# zx81b.net
KiCad netlist of a schematic drawn in EAGLE
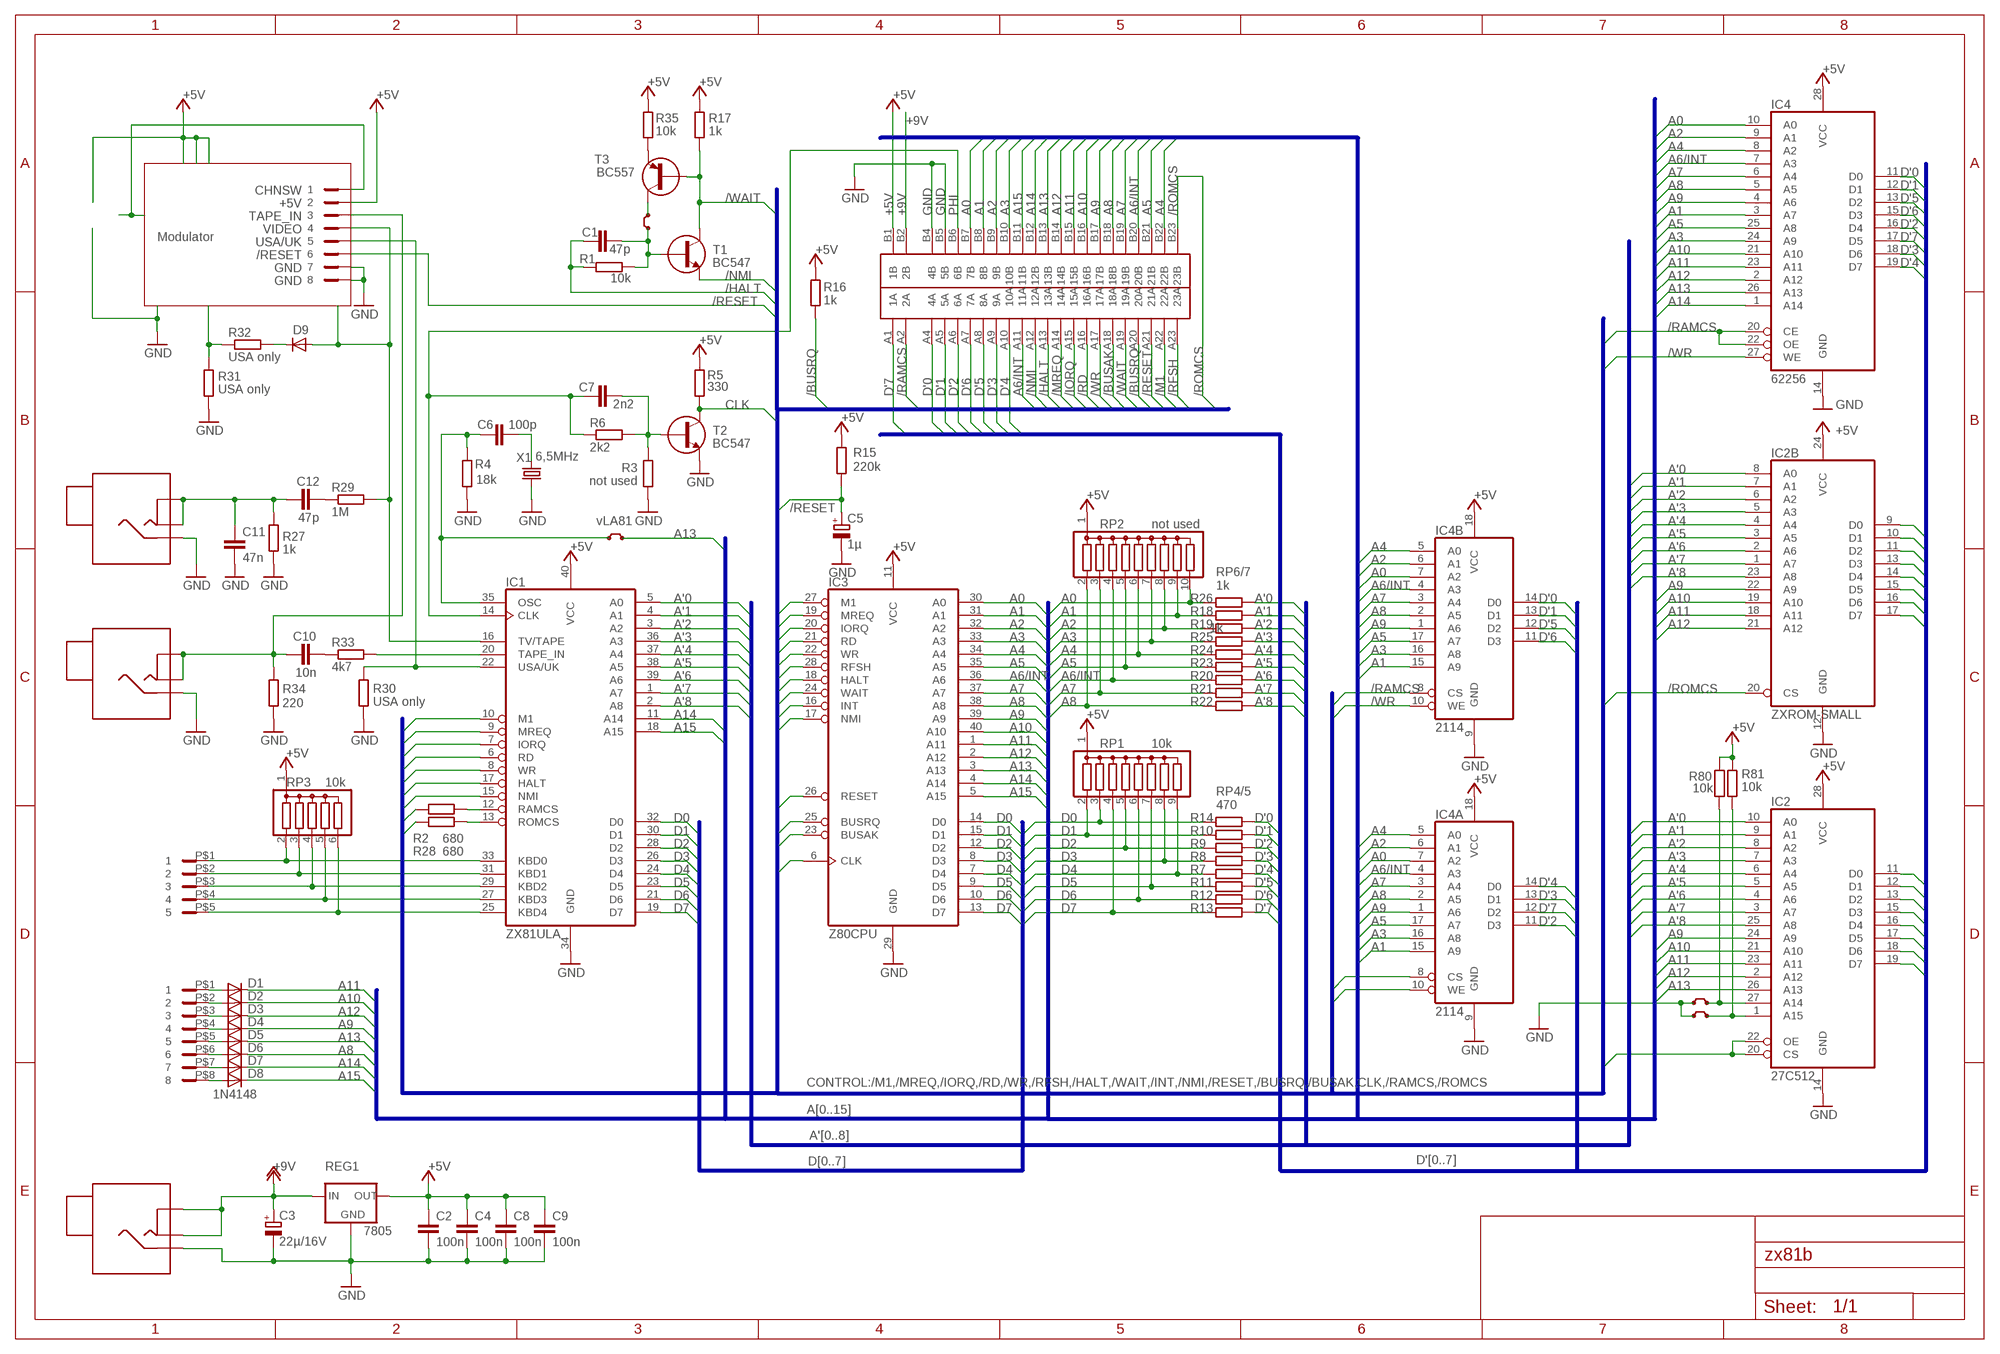
[diagram p0: schematic, sheet 1]

(export (version "E")
  (design (tool "Eeschema 10.0.6"))
  (components
    (comp (ref "C1")
      (value "47p")
      (footprint "eagle-import:C025-025X050")
      (libsource (lib "eagle-import") (part "C"))
    )
    (comp (ref "C2")
      (value "100n")
      (footprint "eagle-import:C025-025X050")
      (libsource (lib "eagle-import") (part "C"))
    )
    (comp (ref "C3")
      (value "22µ/16V")
      (footprint "eagle-import:E5-5")
      (libsource (lib "eagle-import") (part "CPOLE5-5"))
    )
    (comp (ref "C4")
      (value "100n")
      (footprint "eagle-import:C025-025X050")
      (libsource (lib "eagle-import") (part "C"))
    )
    (comp (ref "C5")
      (value "1µ")
      (footprint "eagle-import:E3,8-5")
      (libsource (lib "eagle-import") (part "CPOLE3,8-5"))
    )
    (comp (ref "C6")
      (value "100p")
      (footprint "eagle-import:C025-025X050")
      (libsource (lib "eagle-import") (part "C"))
    )
    (comp (ref "C7")
      (value "2n2")
      (footprint "eagle-import:C025-025X050")
      (libsource (lib "eagle-import") (part "C"))
    )
    (comp (ref "C8")
      (value "100n")
      (footprint "eagle-import:C025-025X050")
      (libsource (lib "eagle-import") (part "C"))
    )
    (comp (ref "C9")
      (value "100n")
      (footprint "eagle-import:C025-025X050")
      (libsource (lib "eagle-import") (part "C"))
    )
    (comp (ref "C10")
      (value "10n")
      (footprint "eagle-import:C025-025X050")
      (libsource (lib "eagle-import") (part "C"))
    )
    (comp (ref "C11")
      (value "47n")
      (footprint "eagle-import:C025-025X050")
      (libsource (lib "eagle-import") (part "C"))
    )
    (comp (ref "C12")
      (value "47p")
      (footprint "eagle-import:C025-025X050")
      (libsource (lib "eagle-import") (part "C"))
    )
    (comp (ref "D1")
      (value "1N4148")
      (footprint "eagle-import:D-TR-10")
      (libsource (lib "eagle-import") (part "DIODEDTR"))
    )
    (comp (ref "D2")
      (value "1N4148")
      (footprint "eagle-import:D-TR-10")
      (libsource (lib "eagle-import") (part "DIODEDTR"))
    )
    (comp (ref "D3")
      (value "1N4148")
      (footprint "eagle-import:D-TR-10")
      (libsource (lib "eagle-import") (part "DIODEDTR"))
    )
    (comp (ref "D4")
      (value "1N4148")
      (footprint "eagle-import:D-TR-10")
      (libsource (lib "eagle-import") (part "DIODEDTR"))
    )
    (comp (ref "D5")
      (value "1N4148")
      (footprint "eagle-import:D-TR-10")
      (libsource (lib "eagle-import") (part "DIODEDTR"))
    )
    (comp (ref "D6")
      (value "1N4148")
      (footprint "eagle-import:D-TR-10")
      (libsource (lib "eagle-import") (part "DIODEDTR"))
    )
    (comp (ref "D7")
      (value "1N4148")
      (footprint "eagle-import:D-TR-10")
      (libsource (lib "eagle-import") (part "DIODEDTR"))
    )
    (comp (ref "D8")
      (value "1N4148")
      (footprint "eagle-import:D-TR-10")
      (libsource (lib "eagle-import") (part "DIODEDTR"))
    )
    (comp (ref "D9")
      (value "DIODED15")
      (footprint "eagle-import:D15")
      (libsource (lib "eagle-import") (part "DIODED15"))
    )
    (comp (ref "IC1")
      (value "ZX81ULA")
      (footprint "eagle-import:DIL40")
      (libsource (lib "eagle-import") (part "ZX81ULA"))
    )
    (comp (ref "IC2")
      (value "27C512")
      (footprint "eagle-import:DIL28")
      (libsource (lib "eagle-import") (part "27C512"))
    )
    (comp (ref "IC2B")
      (value "ZXROM-SMALL")
      (footprint "eagle-import:DIL24")
      (libsource (lib "eagle-import") (part "ZXROM-SMALL"))
    )
    (comp (ref "IC3")
      (value "Z80CPU")
      (footprint "eagle-import:DIL40")
      (libsource (lib "eagle-import") (part "Z80CPU"))
    )
    (comp (ref "IC4")
      (value "62256")
      (footprint "eagle-import:DIL28")
      (libsource (lib "eagle-import") (part "62256"))
    )
    (comp (ref "IC4A")
      (value "2114")
      (footprint "eagle-import:DIL18")
      (libsource (lib "eagle-import") (part "2114"))
    )
    (comp (ref "IC4B")
      (value "2114")
      (footprint "eagle-import:DIL18")
      (libsource (lib "eagle-import") (part "2114"))
    )
    (comp (ref "JP1")
      (value "JUMPER")
      (footprint "eagle-import:JUMPER")
      (libsource (lib "eagle-import") (part "JUMPER"))
    )
    (comp (ref "JP2")
      (value "JUMPER")
      (footprint "eagle-import:JUMPER")
      (libsource (lib "eagle-import") (part "JUMPER"))
    )
    (comp (ref "JP3")
      (value "JUMPER")
      (footprint "eagle-import:JUMPER")
      (libsource (lib "eagle-import") (part "JUMPER"))
    )
    (comp (ref "JP4")
      (value "JUMPER")
      (footprint "eagle-import:JUMPER")
      (libsource (lib "eagle-import") (part "JUMPER"))
    )
    (comp (ref "K1")
      (value "ZX81CONN")
      (footprint "eagle-import:ZX81CON")
      (libsource (lib "eagle-import") (part "ZX81CONN"))
    )
    (comp (ref "K2")
      (value "MIC")
      (footprint "eagle-import:ZXKLINKE")
      (libsource (lib "eagle-import") (part "ZXKLINKE"))
    )
    (comp (ref "K3")
      (value "EAR")
      (footprint "eagle-import:ZXKLINKE")
      (libsource (lib "eagle-import") (part "ZXKLINKE"))
    )
    (comp (ref "K4")
      (value "DCIN")
      (footprint "eagle-import:ZXKLINKE")
      (libsource (lib "eagle-import") (part "ZXKLINKE"))
    )
    (comp (ref "K5")
      (value "PINHEAD-2X4")
      (footprint "eagle-import:PINHEAD2X4")
      (libsource (lib "eagle-import") (part "PINHEAD-2X4"))
    )
    (comp (ref "KB1")
      (value "ZXKBD5CON")
      (footprint "eagle-import:ZXKDB5")
      (libsource (lib "eagle-import") (part "ZXKBD5CON"))
    )
    (comp (ref "KB2")
      (value "ZXKBD8CON")
      (footprint "eagle-import:ZXKBD8")
      (libsource (lib "eagle-import") (part "ZXKBD8CON"))
    )
    (comp (ref "R1")
      (value "10k")
      (footprint "eagle-import:R207_12")
      (libsource (lib "eagle-import") (part "RR207/12"))
    )
    (comp (ref "R2")
      (value "680")
      (footprint "eagle-import:R207_12")
      (libsource (lib "eagle-import") (part "RR207/12"))
    )
    (comp (ref "R3")
      (value "not used")
      (footprint "eagle-import:R207_12")
      (libsource (lib "eagle-import") (part "RR207/12"))
    )
    (comp (ref "R4")
      (value "18k")
      (footprint "eagle-import:R207_12")
      (libsource (lib "eagle-import") (part "RR207/12"))
    )
    (comp (ref "R5")
      (value "330")
      (footprint "eagle-import:R207_12")
      (libsource (lib "eagle-import") (part "RR207/12"))
    )
    (comp (ref "R6")
      (value "2k2")
      (footprint "eagle-import:R207_12")
      (libsource (lib "eagle-import") (part "RR207/12"))
    )
    (comp (ref "R15")
      (value "220k")
      (footprint "eagle-import:R207_12")
      (libsource (lib "eagle-import") (part "RR207/12"))
    )
    (comp (ref "R16")
      (value "1k")
      (footprint "eagle-import:R207_12")
      (libsource (lib "eagle-import") (part "RR207/12"))
    )
    (comp (ref "R17")
      (value "1k")
      (footprint "eagle-import:R207_12")
      (libsource (lib "eagle-import") (part "RR207/12"))
    )
    (comp (ref "R27")
      (value "1k")
      (footprint "eagle-import:R207_12")
      (libsource (lib "eagle-import") (part "RR207/12"))
    )
    (comp (ref "R28")
      (value "680")
      (footprint "eagle-import:R207_12")
      (libsource (lib "eagle-import") (part "RR207/12"))
    )
    (comp (ref "R29")
      (value "1M")
      (footprint "eagle-import:R207_12")
      (libsource (lib "eagle-import") (part "RR207/12"))
    )
    (comp (ref "R30")
      (value "USA only")
      (footprint "eagle-import:R207_12")
      (libsource (lib "eagle-import") (part "RR207/12"))
    )
    (comp (ref "R31")
      (value "USA only")
      (footprint "eagle-import:R207_12")
      (libsource (lib "eagle-import") (part "RR207/12"))
    )
    (comp (ref "R32")
      (value "USA only")
      (footprint "eagle-import:R207_12")
      (libsource (lib "eagle-import") (part "RR207/12"))
    )
    (comp (ref "R33")
      (value "4k7")
      (footprint "eagle-import:R207_12")
      (libsource (lib "eagle-import") (part "RR207/12"))
    )
    (comp (ref "R34")
      (value "220")
      (footprint "eagle-import:R207_12")
      (libsource (lib "eagle-import") (part "RR207/12"))
    )
    (comp (ref "R35")
      (value "10k")
      (footprint "eagle-import:R207_12")
      (libsource (lib "eagle-import") (part "RR207/12"))
    )
    (comp (ref "R80")
      (value "10k")
      (footprint "eagle-import:R207_12")
      (libsource (lib "eagle-import") (part "RR207/12"))
    )
    (comp (ref "R81")
      (value "10k")
      (footprint "eagle-import:R207_12")
      (libsource (lib "eagle-import") (part "RR207/12"))
    )
    (comp (ref "REG1")
      (value "7805")
      (footprint "eagle-import:78XXL")
      (libsource (lib "eagle-import") (part "78XX"))
    )
    (comp (ref "RP1")
      (value "10k")
      (footprint "eagle-import:SIL9")
      (libsource (lib "eagle-import") (part "RSIL8"))
    )
    (comp (ref "RP2")
      (value "not used")
      (footprint "eagle-import:SIL10")
      (libsource (lib "eagle-import") (part "RSIL9"))
    )
    (comp (ref "RP3")
      (value "10k")
      (footprint "eagle-import:SIL6")
      (libsource (lib "eagle-import") (part "RSIL5"))
    )
    (comp (ref "RP4")
      (value "470")
      (footprint "eagle-import:SIL8P")
      (libsource (lib "eagle-import") (part "RSILP4"))
    )
    (comp (ref "RP5")
      (value "470")
      (footprint "eagle-import:SIL8P")
      (libsource (lib "eagle-import") (part "RSILP4"))
    )
    (comp (ref "RP6")
      (value "1k")
      (footprint "eagle-import:SIL8P")
      (libsource (lib "eagle-import") (part "RSILP4"))
    )
    (comp (ref "RP7")
      (value "1k")
      (footprint "eagle-import:SIL10P")
      (libsource (lib "eagle-import") (part "RSILP5"))
    )
    (comp (ref "T1")
      (value "BC547")
      (footprint "eagle-import:TO92")
      (libsource (lib "eagle-import") (part "T-NPN-BC547"))
    )
    (comp (ref "T2")
      (value "BC547")
      (footprint "eagle-import:TO92")
      (libsource (lib "eagle-import") (part "T-NPN-BC547"))
    )
    (comp (ref "T3")
      (value "BC557")
      (footprint "eagle-import:TO92")
      (libsource (lib "eagle-import") (part "T-PNP-BC557"))
    )
    (comp (ref "X1")
      (value "6,5MHz")
      (footprint "eagle-import:HC49")
      (libsource (lib "eagle-import") (part "CRYSTAL"))
    )
  )
  (nets
    (net (code "4") (name "+5V") (class "Default")
      (node (ref "C2") (pin "1") (pinfunction "1_1") (pintype "passive"))
      (node (ref "C4") (pin "1") (pinfunction "1_1") (pintype "passive"))
      (node (ref "C8") (pin "1") (pinfunction "1_1") (pintype "passive"))
      (node (ref "C9") (pin "1") (pinfunction "1_1") (pintype "passive"))
      (node (ref "IC1") (pin "40") (pinfunction "VCC_40") (pintype "power_in"))
      (node (ref "IC2") (pin "28") (pinfunction "VCC_28") (pintype "power_in"))
      (node (ref "IC2B") (pin "24") (pinfunction "VCC_24") (pintype "power_in"))
      (node (ref "IC3") (pin "11") (pinfunction "VCC_11") (pintype "power_in"))
      (node (ref "IC4") (pin "28") (pinfunction "VCC_28") (pintype "power_in"))
      (node (ref "IC4A") (pin "18") (pinfunction "VCC_18") (pintype "power_in"))
      (node (ref "IC4B") (pin "18") (pinfunction "VCC_18") (pintype "power_in"))
      (node (ref "K1") (pin "B1") (pinfunction "1B_B1") (pintype "bidirectional"))
      (node (ref "K5") (pin "2") (pinfunction "2_2") (pintype "bidirectional"))
      (node (ref "R15") (pin "2") (pinfunction "2_2") (pintype "passive"))
      (node (ref "R16") (pin "1") (pinfunction "1_1") (pintype "passive"))
      (node (ref "R17") (pin "2") (pinfunction "2_2") (pintype "passive"))
      (node (ref "R35") (pin "2") (pinfunction "2_2") (pintype "passive"))
      (node (ref "R5") (pin "2") (pinfunction "2_2") (pintype "passive"))
      (node (ref "R80") (pin "2") (pinfunction "2_2") (pintype "passive"))
      (node (ref "R81") (pin "2") (pinfunction "2_2") (pintype "passive"))
      (node (ref "REG1") (pin "OUT") (pinfunction "OUT_OUT") (pintype "passive"))
      (node (ref "RP1") (pin "1") (pinfunction "1_1") (pintype "passive"))
      (node (ref "RP2") (pin "1") (pinfunction "1_1") (pintype "passive"))
      (node (ref "RP3") (pin "1") (pinfunction "1_1") (pintype "passive"))
    )
    (net (code "5") (name "+9V") (class "Default")
      (node (ref "C3") (pin "+") (pinfunction "+_+") (pintype "passive"))
      (node (ref "K1") (pin "B2") (pinfunction "2B_B2") (pintype "bidirectional"))
      (node (ref "K4") (pin "1") (pinfunction "P$1_1") (pintype "bidirectional"))
      (node (ref "K4") (pin "1'") (pinfunction "P$1'_1'") (pintype "bidirectional"))
      (node (ref "REG1") (pin "IN") (pinfunction "IN_IN") (pintype "input"))
    )
    (net (code "6") (name "/A'0") (class "Default")
      (node (ref "IC1") (pin "5") (pinfunction "A0_5") (pintype "output"))
      (node (ref "IC2") (pin "10") (pinfunction "A0_10") (pintype "input"))
      (node (ref "IC2B") (pin "8") (pinfunction "A0_8") (pintype "input"))
      (node (ref "RP6") (pin "7") (pinfunction "1_7") (pintype "passive"))
    )
    (net (code "7") (name "/A'1") (class "Default")
      (node (ref "IC1") (pin "4") (pinfunction "A1_4") (pintype "output"))
      (node (ref "IC2") (pin "9") (pinfunction "A1_9") (pintype "input"))
      (node (ref "IC2B") (pin "7") (pinfunction "A1_7") (pintype "input"))
      (node (ref "RP7") (pin "2") (pinfunction "2_2") (pintype "passive"))
    )
    (net (code "8") (name "/A'2") (class "Default")
      (node (ref "IC1") (pin "3") (pinfunction "A2_3") (pintype "output"))
      (node (ref "IC2") (pin "8") (pinfunction "A2_8") (pintype "input"))
      (node (ref "IC2B") (pin "6") (pinfunction "A2_6") (pintype "input"))
      (node (ref "RP7") (pin "3") (pinfunction "1_3") (pintype "passive"))
    )
    (net (code "9") (name "/A'3") (class "Default")
      (node (ref "IC1") (pin "36") (pinfunction "A3_36") (pintype "output"))
      (node (ref "IC2") (pin "7") (pinfunction "A3_7") (pintype "input"))
      (node (ref "IC2B") (pin "5") (pinfunction "A3_5") (pintype "input"))
      (node (ref "RP6") (pin "5") (pinfunction "1_5") (pintype "passive"))
    )
    (net (code "10") (name "/A'4") (class "Default")
      (node (ref "IC1") (pin "37") (pinfunction "A4_37") (pintype "output"))
      (node (ref "IC2") (pin "6") (pinfunction "A4_6") (pintype "input"))
      (node (ref "IC2B") (pin "4") (pinfunction "A4_4") (pintype "input"))
      (node (ref "RP6") (pin "3") (pinfunction "1_3") (pintype "passive"))
    )
    (net (code "11") (name "/A'5") (class "Default")
      (node (ref "IC1") (pin "38") (pinfunction "A5_38") (pintype "output"))
      (node (ref "IC2") (pin "5") (pinfunction "A5_5") (pintype "input"))
      (node (ref "IC2B") (pin "3") (pinfunction "A5_3") (pintype "input"))
      (node (ref "RP6") (pin "1") (pinfunction "1_1") (pintype "passive"))
    )
    (net (code "12") (name "/A'6") (class "Default")
      (node (ref "IC1") (pin "39") (pinfunction "A6_39") (pintype "output"))
      (node (ref "IC2") (pin "4") (pinfunction "A6_4") (pintype "input"))
      (node (ref "IC2B") (pin "2") (pinfunction "A6_2") (pintype "input"))
      (node (ref "RP7") (pin "5") (pinfunction "1_5") (pintype "passive"))
    )
    (net (code "13") (name "/A'7") (class "Default")
      (node (ref "IC1") (pin "1") (pinfunction "A7_1") (pintype "output"))
      (node (ref "IC2") (pin "3") (pinfunction "A7_3") (pintype "input"))
      (node (ref "IC2B") (pin "1") (pinfunction "A7_1") (pintype "input"))
      (node (ref "RP7") (pin "7") (pinfunction "1_7") (pintype "passive"))
    )
    (net (code "14") (name "/A'8") (class "Default")
      (node (ref "IC1") (pin "2") (pinfunction "A8_2") (pintype "output"))
      (node (ref "IC2") (pin "25") (pinfunction "A8_25") (pintype "input"))
      (node (ref "IC2B") (pin "23") (pinfunction "A8_23") (pintype "input"))
      (node (ref "RP7") (pin "9") (pinfunction "1_9") (pintype "passive"))
    )
    (net (code "16") (name "/A0") (class "Default")
      (node (ref "IC3") (pin "30") (pinfunction "A0_30") (pintype "output"))
      (node (ref "IC4") (pin "10") (pinfunction "A0_10") (pintype "input"))
      (node (ref "IC4A") (pin "7") (pinfunction "A2_7") (pintype "output"))
      (node (ref "IC4B") (pin "7") (pinfunction "A2_7") (pintype "output"))
      (node (ref "K1") (pin "B7") (pinfunction "7B_B7") (pintype "bidirectional"))
      (node (ref "RP2") (pin "10") (pinfunction "10_10") (pintype "passive"))
      (node (ref "RP6") (pin "8") (pinfunction "2_8") (pintype "passive"))
    )
    (net (code "17") (name "/A1") (class "Default")
      (node (ref "IC3") (pin "31") (pinfunction "A1_31") (pintype "output"))
      (node (ref "IC4") (pin "3") (pinfunction "A7_3") (pintype "input"))
      (node (ref "IC4A") (pin "15") (pinfunction "A9_15") (pintype "output"))
      (node (ref "IC4B") (pin "15") (pinfunction "A9_15") (pintype "output"))
      (node (ref "K1") (pin "B8") (pinfunction "8B_B8") (pintype "bidirectional"))
      (node (ref "RP2") (pin "9") (pinfunction "9_9") (pintype "passive"))
      (node (ref "RP7") (pin "1") (pinfunction "1_1") (pintype "passive"))
    )
    (net (code "18") (name "/A2") (class "Default")
      (node (ref "IC3") (pin "32") (pinfunction "A2_32") (pintype "output"))
      (node (ref "IC4") (pin "9") (pinfunction "A1_9") (pintype "input"))
      (node (ref "IC4A") (pin "6") (pinfunction "A1_6") (pintype "output"))
      (node (ref "IC4B") (pin "6") (pinfunction "A1_6") (pintype "output"))
      (node (ref "K1") (pin "B9") (pinfunction "9B_B9") (pintype "bidirectional"))
      (node (ref "RP2") (pin "8") (pinfunction "8_8") (pintype "passive"))
      (node (ref "RP7") (pin "4") (pinfunction "2_4") (pintype "passive"))
    )
    (net (code "19") (name "/A3") (class "Default")
      (node (ref "IC3") (pin "33") (pinfunction "A3_33") (pintype "output"))
      (node (ref "IC4") (pin "24") (pinfunction "A9_24") (pintype "input"))
      (node (ref "IC4A") (pin "16") (pinfunction "A8_16") (pintype "output"))
      (node (ref "IC4B") (pin "16") (pinfunction "A8_16") (pintype "output"))
      (node (ref "K1") (pin "B10") (pinfunction "10B_B10") (pintype "bidirectional"))
      (node (ref "RP2") (pin "7") (pinfunction "7_7") (pintype "passive"))
      (node (ref "RP6") (pin "6") (pinfunction "2_6") (pintype "passive"))
    )
    (net (code "20") (name "/A4") (class "Default")
      (node (ref "IC3") (pin "34") (pinfunction "A4_34") (pintype "output"))
      (node (ref "IC4") (pin "8") (pinfunction "A2_8") (pintype "input"))
      (node (ref "IC4A") (pin "5") (pinfunction "A0_5") (pintype "output"))
      (node (ref "IC4B") (pin "5") (pinfunction "A0_5") (pintype "output"))
      (node (ref "K1") (pin "B22") (pinfunction "22B_B22") (pintype "bidirectional"))
      (node (ref "RP2") (pin "6") (pinfunction "6_6") (pintype "passive"))
      (node (ref "RP6") (pin "4") (pinfunction "2_4") (pintype "passive"))
    )
    (net (code "21") (name "/A5") (class "Default")
      (node (ref "IC3") (pin "35") (pinfunction "A5_35") (pintype "output"))
      (node (ref "IC4") (pin "25") (pinfunction "A8_25") (pintype "input"))
      (node (ref "IC4A") (pin "17") (pinfunction "A7_17") (pintype "output"))
      (node (ref "IC4B") (pin "17") (pinfunction "A7_17") (pintype "output"))
      (node (ref "K1") (pin "B21") (pinfunction "21B_B21") (pintype "bidirectional"))
      (node (ref "RP2") (pin "5") (pinfunction "5_5") (pintype "passive"))
      (node (ref "RP6") (pin "2") (pinfunction "2_2") (pintype "passive"))
    )
    (net (code "22") (name "/A6{slash}INT") (class "Default")
      (node (ref "IC3") (pin "16") (pinfunction "INT_16") (pintype "input"))
      (node (ref "IC3") (pin "36") (pinfunction "A6_36") (pintype "output"))
      (node (ref "IC4") (pin "7") (pinfunction "A3_7") (pintype "input"))
      (node (ref "IC4A") (pin "4") (pinfunction "A3_4") (pintype "output"))
      (node (ref "IC4B") (pin "4") (pinfunction "A3_4") (pintype "output"))
      (node (ref "K1") (pin "A11") (pinfunction "11A_A11") (pintype "bidirectional"))
      (node (ref "K1") (pin "B20") (pinfunction "20B_B20") (pintype "bidirectional"))
      (node (ref "RP2") (pin "4") (pinfunction "4_4") (pintype "passive"))
      (node (ref "RP7") (pin "6") (pinfunction "2_6") (pintype "passive"))
    )
    (net (code "23") (name "/A7") (class "Default")
      (node (ref "IC3") (pin "37") (pinfunction "A7_37") (pintype "output"))
      (node (ref "IC4") (pin "6") (pinfunction "A4_6") (pintype "input"))
      (node (ref "IC4A") (pin "3") (pinfunction "A4_3") (pintype "output"))
      (node (ref "IC4B") (pin "3") (pinfunction "A4_3") (pintype "output"))
      (node (ref "K1") (pin "B19") (pinfunction "19B_B19") (pintype "bidirectional"))
      (node (ref "RP2") (pin "3") (pinfunction "3_3") (pintype "passive"))
      (node (ref "RP7") (pin "8") (pinfunction "2_8") (pintype "passive"))
    )
    (net (code "24") (name "/A8") (class "Default")
      (node (ref "D6") (pin "C") (pinfunction "C_C") (pintype "passive"))
      (node (ref "IC3") (pin "38") (pinfunction "A8_38") (pintype "output"))
      (node (ref "IC4") (pin "5") (pinfunction "A5_5") (pintype "input"))
      (node (ref "IC4A") (pin "2") (pinfunction "A5_2") (pintype "output"))
      (node (ref "IC4B") (pin "2") (pinfunction "A5_2") (pintype "output"))
      (node (ref "K1") (pin "B18") (pinfunction "18B_B18") (pintype "bidirectional"))
      (node (ref "RP2") (pin "2") (pinfunction "2_2") (pintype "passive"))
      (node (ref "RP7") (pin "10") (pinfunction "2_10") (pintype "passive"))
    )
    (net (code "25") (name "/A9") (class "Default")
      (node (ref "D4") (pin "C") (pinfunction "C_C") (pintype "passive"))
      (node (ref "IC2") (pin "24") (pinfunction "A9_24") (pintype "input"))
      (node (ref "IC2B") (pin "22") (pinfunction "A9_22") (pintype "input"))
      (node (ref "IC3") (pin "39") (pinfunction "A9_39") (pintype "output"))
      (node (ref "IC4") (pin "4") (pinfunction "A6_4") (pintype "input"))
      (node (ref "IC4A") (pin "1") (pinfunction "A6_1") (pintype "output"))
      (node (ref "IC4B") (pin "1") (pinfunction "A6_1") (pintype "output"))
      (node (ref "K1") (pin "B17") (pinfunction "17B_B17") (pintype "bidirectional"))
    )
    (net (code "26") (name "/A10") (class "Default")
      (node (ref "D2") (pin "C") (pinfunction "C_C") (pintype "passive"))
      (node (ref "IC2") (pin "21") (pinfunction "A10_21") (pintype "input"))
      (node (ref "IC2B") (pin "19") (pinfunction "A10_19") (pintype "input"))
      (node (ref "IC3") (pin "40") (pinfunction "A10_40") (pintype "output"))
      (node (ref "IC4") (pin "21") (pinfunction "A10_21") (pintype "input"))
      (node (ref "K1") (pin "B16") (pinfunction "16B_B16") (pintype "bidirectional"))
    )
    (net (code "27") (name "/A11") (class "Default")
      (node (ref "D1") (pin "C") (pinfunction "C_C") (pintype "passive"))
      (node (ref "IC2") (pin "23") (pinfunction "A11_23") (pintype "input"))
      (node (ref "IC2B") (pin "18") (pinfunction "A11_18") (pintype "input"))
      (node (ref "IC3") (pin "1") (pinfunction "A11_1") (pintype "output"))
      (node (ref "IC4") (pin "23") (pinfunction "A11_23") (pintype "input"))
      (node (ref "K1") (pin "B15") (pinfunction "15B_B15") (pintype "bidirectional"))
    )
    (net (code "28") (name "/A12") (class "Default")
      (node (ref "D3") (pin "C") (pinfunction "C_C") (pintype "passive"))
      (node (ref "IC2") (pin "2") (pinfunction "A12_2") (pintype "input"))
      (node (ref "IC2B") (pin "21") (pinfunction "A12_21") (pintype "input"))
      (node (ref "IC3") (pin "2") (pinfunction "A12_2") (pintype "output"))
      (node (ref "IC4") (pin "2") (pinfunction "A12_2") (pintype "input"))
      (node (ref "K1") (pin "B14") (pinfunction "14B_B14") (pintype "bidirectional"))
    )
    (net (code "29") (name "/A13") (class "Default")
      (node (ref "D5") (pin "C") (pinfunction "C_C") (pintype "passive"))
      (node (ref "IC2") (pin "26") (pinfunction "A13_26") (pintype "input"))
      (node (ref "IC3") (pin "3") (pinfunction "A13_3") (pintype "output"))
      (node (ref "IC4") (pin "26") (pinfunction "A13_26") (pintype "input"))
      (node (ref "JP3") (pin "2") (pinfunction "P$2_2") (pintype "bidirectional"))
      (node (ref "K1") (pin "B13") (pinfunction "13B_B13") (pintype "bidirectional"))
    )
    (net (code "30") (name "/A14") (class "Default")
      (node (ref "D7") (pin "C") (pinfunction "C_C") (pintype "passive"))
      (node (ref "IC1") (pin "11") (pinfunction "A14_11") (pintype "output"))
      (node (ref "IC3") (pin "4") (pinfunction "A14_4") (pintype "output"))
      (node (ref "IC4") (pin "1") (pinfunction "A14_1") (pintype "input"))
      (node (ref "K1") (pin "B12") (pinfunction "12B_B12") (pintype "bidirectional"))
    )
    (net (code "31") (name "/A15") (class "Default")
      (node (ref "D8") (pin "C") (pinfunction "C_C") (pintype "passive"))
      (node (ref "IC1") (pin "18") (pinfunction "A15_18") (pintype "output"))
      (node (ref "IC3") (pin "5") (pinfunction "A15_5") (pintype "output"))
      (node (ref "K1") (pin "B11") (pinfunction "11B_B11") (pintype "bidirectional"))
    )
    (net (code "33") (name "/CHNSW") (class "Default")
      (node (ref "K5") (pin "1") (pinfunction "1_1") (pintype "bidirectional"))
    )
    (net (code "34") (name "/CLK") (class "Default")
      (node (ref "IC3") (pin "6") (pinfunction "CLK_6") (pintype "input"))
      (node (ref "R5") (pin "1") (pinfunction "1_1") (pintype "passive"))
      (node (ref "T2") (pin "C") (pinfunction "C_C") (pintype "passive"))
    )
    (net (code "35") (name "/D'0") (class "Default")
      (node (ref "IC2") (pin "11") (pinfunction "D0_11") (pintype "bidirectional"))
      (node (ref "IC2B") (pin "9") (pinfunction "D0_9") (pintype "output"))
      (node (ref "IC4") (pin "11") (pinfunction "D0_11") (pintype "bidirectional"))
      (node (ref "IC4B") (pin "14") (pinfunction "D0_14") (pintype "bidirectional"))
      (node (ref "K1") (pin "A4") (pinfunction "4A_A4") (pintype "bidirectional"))
      (node (ref "RP5") (pin "8") (pinfunction "2_8") (pintype "passive"))
    )
    (net (code "36") (name "/D'1") (class "Default")
      (node (ref "IC2") (pin "12") (pinfunction "D1_12") (pintype "bidirectional"))
      (node (ref "IC2B") (pin "10") (pinfunction "D1_10") (pintype "output"))
      (node (ref "IC4") (pin "12") (pinfunction "D1_12") (pintype "bidirectional"))
      (node (ref "IC4B") (pin "13") (pinfunction "D1_13") (pintype "bidirectional"))
      (node (ref "K1") (pin "A5") (pinfunction "5A_A5") (pintype "bidirectional"))
      (node (ref "RP4") (pin "8") (pinfunction "2_8") (pintype "passive"))
    )
    (net (code "37") (name "/D'2") (class "Default")
      (node (ref "IC2") (pin "13") (pinfunction "D2_13") (pintype "bidirectional"))
      (node (ref "IC2B") (pin "11") (pinfunction "D2_11") (pintype "output"))
      (node (ref "IC4") (pin "16") (pinfunction "D4_16") (pintype "bidirectional"))
      (node (ref "IC4A") (pin "11") (pinfunction "D3_11") (pintype "bidirectional"))
      (node (ref "K1") (pin "A6") (pinfunction "6A_A6") (pintype "bidirectional"))
      (node (ref "RP4") (pin "6") (pinfunction "2_6") (pintype "passive"))
    )
    (net (code "38") (name "/D'3") (class "Default")
      (node (ref "IC2") (pin "15") (pinfunction "D3_15") (pintype "bidirectional"))
      (node (ref "IC2B") (pin "13") (pinfunction "D3_13") (pintype "output"))
      (node (ref "IC4") (pin "18") (pinfunction "D6_18") (pintype "bidirectional"))
      (node (ref "IC4A") (pin "13") (pinfunction "D1_13") (pintype "bidirectional"))
      (node (ref "K1") (pin "A9") (pinfunction "9A_A9") (pintype "bidirectional"))
      (node (ref "RP4") (pin "4") (pinfunction "2_4") (pintype "passive"))
    )
    (net (code "39") (name "/D'4") (class "Default")
      (node (ref "IC2") (pin "16") (pinfunction "D4_16") (pintype "bidirectional"))
      (node (ref "IC2B") (pin "14") (pinfunction "D4_14") (pintype "output"))
      (node (ref "IC4") (pin "19") (pinfunction "D7_19") (pintype "bidirectional"))
      (node (ref "IC4A") (pin "14") (pinfunction "D0_14") (pintype "bidirectional"))
      (node (ref "K1") (pin "A10") (pinfunction "10A_A10") (pintype "bidirectional"))
      (node (ref "RP4") (pin "1") (pinfunction "1_1") (pintype "passive"))
    )
    (net (code "40") (name "/D'5") (class "Default")
      (node (ref "IC2") (pin "17") (pinfunction "D5_17") (pintype "bidirectional"))
      (node (ref "IC2B") (pin "15") (pinfunction "D5_15") (pintype "output"))
      (node (ref "IC4") (pin "13") (pinfunction "D2_13") (pintype "bidirectional"))
      (node (ref "IC4B") (pin "12") (pinfunction "D2_12") (pintype "bidirectional"))
      (node (ref "K1") (pin "A8") (pinfunction "8A_A8") (pintype "bidirectional"))
      (node (ref "RP5") (pin "1") (pinfunction "1_1") (pintype "passive"))
    )
    (net (code "41") (name "/D'6") (class "Default")
      (node (ref "IC2") (pin "18") (pinfunction "D6_18") (pintype "bidirectional"))
      (node (ref "IC2B") (pin "16") (pinfunction "D6_16") (pintype "output"))
      (node (ref "IC4") (pin "15") (pinfunction "D3_15") (pintype "bidirectional"))
      (node (ref "IC4B") (pin "11") (pinfunction "D3_11") (pintype "bidirectional"))
      (node (ref "K1") (pin "A7") (pinfunction "7A_A7") (pintype "bidirectional"))
      (node (ref "RP5") (pin "4") (pinfunction "2_4") (pintype "passive"))
    )
    (net (code "42") (name "/D'7") (class "Default")
      (node (ref "IC2") (pin "19") (pinfunction "D7_19") (pintype "bidirectional"))
      (node (ref "IC2B") (pin "17") (pinfunction "D7_17") (pintype "output"))
      (node (ref "IC4") (pin "17") (pinfunction "D5_17") (pintype "bidirectional"))
      (node (ref "IC4A") (pin "12") (pinfunction "D2_12") (pintype "bidirectional"))
      (node (ref "K1") (pin "A1") (pinfunction "1A_A1") (pintype "bidirectional"))
      (node (ref "RP5") (pin "5") (pinfunction "1_5") (pintype "passive"))
    )
    (net (code "44") (name "/D0") (class "Default")
      (node (ref "IC1") (pin "32") (pinfunction "D0_32") (pintype "bidirectional"))
      (node (ref "IC3") (pin "14") (pinfunction "D0_14") (pintype "bidirectional"))
      (node (ref "RP1") (pin "3") (pinfunction "3_3") (pintype "passive"))
      (node (ref "RP5") (pin "7") (pinfunction "1_7") (pintype "passive"))
    )
    (net (code "45") (name "/D1") (class "Default")
      (node (ref "IC1") (pin "30") (pinfunction "D1_30") (pintype "bidirectional"))
      (node (ref "IC3") (pin "15") (pinfunction "D1_15") (pintype "bidirectional"))
      (node (ref "RP1") (pin "2") (pinfunction "2_2") (pintype "passive"))
      (node (ref "RP4") (pin "7") (pinfunction "1_7") (pintype "passive"))
    )
    (net (code "46") (name "/D2") (class "Default")
      (node (ref "IC1") (pin "28") (pinfunction "D2_28") (pintype "bidirectional"))
      (node (ref "IC3") (pin "12") (pinfunction "D2_12") (pintype "bidirectional"))
      (node (ref "RP1") (pin "5") (pinfunction "5_5") (pintype "passive"))
      (node (ref "RP4") (pin "5") (pinfunction "1_5") (pintype "passive"))
    )
    (net (code "47") (name "/D3") (class "Default")
      (node (ref "IC1") (pin "26") (pinfunction "D3_26") (pintype "bidirectional"))
      (node (ref "IC3") (pin "8") (pinfunction "D3_8") (pintype "bidirectional"))
      (node (ref "RP1") (pin "8") (pinfunction "8_8") (pintype "passive"))
      (node (ref "RP4") (pin "3") (pinfunction "1_3") (pintype "passive"))
    )
    (net (code "48") (name "/D4") (class "Default")
      (node (ref "IC1") (pin "24") (pinfunction "D4_24") (pintype "bidirectional"))
      (node (ref "IC3") (pin "7") (pinfunction "D4_7") (pintype "bidirectional"))
      (node (ref "RP1") (pin "9") (pinfunction "9_9") (pintype "passive"))
      (node (ref "RP4") (pin "2") (pinfunction "2_2") (pintype "passive"))
    )
    (net (code "49") (name "/D5") (class "Default")
      (node (ref "IC1") (pin "23") (pinfunction "D5_23") (pintype "bidirectional"))
      (node (ref "IC3") (pin "9") (pinfunction "D5_9") (pintype "bidirectional"))
      (node (ref "RP1") (pin "7") (pinfunction "7_7") (pintype "passive"))
      (node (ref "RP5") (pin "2") (pinfunction "2_2") (pintype "passive"))
    )
    (net (code "50") (name "/D6") (class "Default")
      (node (ref "IC1") (pin "21") (pinfunction "D6_21") (pintype "bidirectional"))
      (node (ref "IC3") (pin "10") (pinfunction "D6_10") (pintype "bidirectional"))
      (node (ref "RP1") (pin "6") (pinfunction "6_6") (pintype "passive"))
      (node (ref "RP5") (pin "3") (pinfunction "1_3") (pintype "passive"))
    )
    (net (code "51") (name "/D7") (class "Default")
      (node (ref "IC1") (pin "19") (pinfunction "D7_19") (pintype "bidirectional"))
      (node (ref "IC3") (pin "13") (pinfunction "D7_13") (pintype "bidirectional"))
      (node (ref "RP1") (pin "4") (pinfunction "4_4") (pintype "passive"))
      (node (ref "RP5") (pin "6") (pinfunction "2_6") (pintype "passive"))
    )
    (net (code "53") (name "/PHI") (class "Default")
      (node (ref "C7") (pin "1") (pinfunction "1_1") (pintype "passive"))
      (node (ref "IC1") (pin "14") (pinfunction "CLK_14") (pintype "input"))
      (node (ref "K1") (pin "B6") (pinfunction "6B_B6") (pintype "bidirectional"))
      (node (ref "R6") (pin "1") (pinfunction "1_1") (pintype "passive"))
    )
    (net (code "54") (name "/TAPE_IN") (class "Default")
      (node (ref "C10") (pin "1") (pinfunction "1_1") (pintype "passive"))
      (node (ref "K3") (pin "1") (pinfunction "P$1_1") (pintype "bidirectional"))
      (node (ref "K3") (pin "1'") (pinfunction "P$1'_1'") (pintype "bidirectional"))
      (node (ref "K5") (pin "3") (pinfunction "3_3") (pintype "bidirectional"))
      (node (ref "R34") (pin "2") (pinfunction "2_2") (pintype "passive"))
    )
    (net (code "55") (name "/USA{slash}UK") (class "Default")
      (node (ref "IC1") (pin "22") (pinfunction "USA/UK_22") (pintype "output"))
      (node (ref "K5") (pin "5") (pinfunction "5_5") (pintype "bidirectional"))
      (node (ref "R30") (pin "1") (pinfunction "1_1") (pintype "passive"))
    )
    (net (code "56") (name "/VIDEO") (class "Default")
      (node (ref "D9") (pin "A") (pinfunction "A_A") (pintype "passive"))
      (node (ref "IC1") (pin "16") (pinfunction "TV/TAPE_16") (pintype "output"))
      (node (ref "K5") (pin "4") (pinfunction "4_4") (pintype "bidirectional"))
      (node (ref "R29") (pin "2") (pinfunction "2_2") (pintype "passive"))
    )
    (net (code "58") (name "/{slash}BUSAK") (class "Default")
      (node (ref "IC3") (pin "23") (pinfunction "BUSAK_23") (pintype "output"))
      (node (ref "K1") (pin "A18") (pinfunction "18A_A18") (pintype "bidirectional"))
    )
    (net (code "59") (name "/{slash}BUSRQ") (class "Default")
      (node (ref "IC3") (pin "25") (pinfunction "BUSRQ_25") (pintype "input"))
      (node (ref "K1") (pin "A20") (pinfunction "20A_A20") (pintype "bidirectional"))
      (node (ref "R16") (pin "2") (pinfunction "2_2") (pintype "passive"))
    )
    (net (code "60") (name "/{slash}HALT") (class "Default")
      (node (ref "C1") (pin "1") (pinfunction "1_1") (pintype "passive"))
      (node (ref "IC1") (pin "17") (pinfunction "HALT_17") (pintype "output"))
      (node (ref "IC3") (pin "18") (pinfunction "HALT_18") (pintype "output"))
      (node (ref "K1") (pin "A13") (pinfunction "13A_A13") (pintype "bidirectional"))
      (node (ref "R1") (pin "1") (pinfunction "1_1") (pintype "passive"))
    )
    (net (code "61") (name "/{slash}IORQ") (class "Default")
      (node (ref "IC1") (pin "7") (pinfunction "IORQ_7") (pintype "output"))
      (node (ref "IC3") (pin "20") (pinfunction "IORQ_20") (pintype "output"))
      (node (ref "K1") (pin "A15") (pinfunction "15A_A15") (pintype "bidirectional"))
    )
    (net (code "62") (name "/{slash}M1") (class "Default")
      (node (ref "IC1") (pin "10") (pinfunction "M1_10") (pintype "output"))
      (node (ref "IC3") (pin "27") (pinfunction "M1_27") (pintype "output"))
      (node (ref "K1") (pin "A22") (pinfunction "22A_A22") (pintype "bidirectional"))
    )
    (net (code "63") (name "/{slash}MREQ") (class "Default")
      (node (ref "IC1") (pin "9") (pinfunction "MREQ_9") (pintype "output"))
      (node (ref "IC3") (pin "19") (pinfunction "MREQ_19") (pintype "output"))
      (node (ref "K1") (pin "A14") (pinfunction "14A_A14") (pintype "bidirectional"))
    )
    (net (code "64") (name "/{slash}NMI") (class "Default")
      (node (ref "IC1") (pin "15") (pinfunction "NMI_15") (pintype "input"))
      (node (ref "IC3") (pin "17") (pinfunction "NMI_17") (pintype "input"))
      (node (ref "K1") (pin "A12") (pinfunction "12A_A12") (pintype "bidirectional"))
      (node (ref "T1") (pin "E") (pinfunction "E_E") (pintype "passive"))
    )
    (net (code "65") (name "/{slash}RAMCS") (class "Default")
      (node (ref "IC4") (pin "20") (pinfunction "CE_20") (pintype "input"))
      (node (ref "IC4") (pin "22") (pinfunction "OE_22") (pintype "input"))
      (node (ref "IC4A") (pin "8") (pinfunction "CS_8") (pintype "output"))
      (node (ref "IC4B") (pin "8") (pinfunction "CS_8") (pintype "output"))
      (node (ref "K1") (pin "A2") (pinfunction "2A_A2") (pintype "bidirectional"))
      (node (ref "R2") (pin "2") (pinfunction "2_2") (pintype "passive"))
    )
    (net (code "66") (name "/{slash}RD") (class "Default")
      (node (ref "IC1") (pin "6") (pinfunction "RD_6") (pintype "output"))
      (node (ref "IC3") (pin "21") (pinfunction "RD_21") (pintype "output"))
      (node (ref "K1") (pin "A16") (pinfunction "16A_A16") (pintype "bidirectional"))
    )
    (net (code "67") (name "/{slash}RESET") (class "Default")
      (node (ref "C5") (pin "+") (pinfunction "+_+") (pintype "passive"))
      (node (ref "IC3") (pin "26") (pinfunction "RESET_26") (pintype "input"))
      (node (ref "K1") (pin "A21") (pinfunction "21A_A21") (pintype "bidirectional"))
      (node (ref "K5") (pin "6") (pinfunction "6_6") (pintype "bidirectional"))
      (node (ref "R15") (pin "1") (pinfunction "1_1") (pintype "passive"))
    )
    (net (code "68") (name "/{slash}RFSH") (class "Default")
      (node (ref "IC3") (pin "28") (pinfunction "RFSH_28") (pintype "output"))
      (node (ref "K1") (pin "A23") (pinfunction "23A_A23") (pintype "bidirectional"))
    )
    (net (code "69") (name "/{slash}ROMCS") (class "Default")
      (node (ref "IC2") (pin "20") (pinfunction "CS_20") (pintype "input"))
      (node (ref "IC2") (pin "22") (pinfunction "OE_22") (pintype "input"))
      (node (ref "IC2B") (pin "20") (pinfunction "CS_20") (pintype "output"))
      (node (ref "K1") (pin "B23") (pinfunction "23B_B23") (pintype "bidirectional"))
      (node (ref "R28") (pin "2") (pinfunction "2_2") (pintype "passive"))
    )
    (net (code "70") (name "/{slash}WAIT") (class "Default")
      (node (ref "IC3") (pin "24") (pinfunction "WAIT_24") (pintype "input"))
      (node (ref "K1") (pin "A19") (pinfunction "19A_A19") (pintype "bidirectional"))
      (node (ref "R17") (pin "1") (pinfunction "1_1") (pintype "passive"))
      (node (ref "T1") (pin "C") (pinfunction "C_C") (pintype "passive"))
      (node (ref "T3") (pin "B") (pinfunction "B_B") (pintype "passive"))
    )
    (net (code "71") (name "/{slash}WR") (class "Default")
      (node (ref "IC1") (pin "8") (pinfunction "WR_8") (pintype "output"))
      (node (ref "IC3") (pin "22") (pinfunction "WR_22") (pintype "output"))
      (node (ref "IC4") (pin "27") (pinfunction "WE_27") (pintype "input"))
      (node (ref "IC4A") (pin "10") (pinfunction "WE_10") (pintype "output"))
      (node (ref "IC4B") (pin "10") (pinfunction "WE_10") (pintype "output"))
      (node (ref "K1") (pin "A17") (pinfunction "17A_A17") (pintype "bidirectional"))
    )
    (net (code "72") (name "GND") (class "Default")
      (node (ref "C11") (pin "2") (pinfunction "2_2") (pintype "passive"))
      (node (ref "C2") (pin "2") (pinfunction "2_2") (pintype "passive"))
      (node (ref "C3") (pin "-") (pinfunction "-_-") (pintype "passive"))
      (node (ref "C4") (pin "2") (pinfunction "2_2") (pintype "passive"))
      (node (ref "C5") (pin "-") (pinfunction "-_-") (pintype "passive"))
      (node (ref "C8") (pin "2") (pinfunction "2_2") (pintype "passive"))
      (node (ref "C9") (pin "2") (pinfunction "2_2") (pintype "passive"))
      (node (ref "IC1") (pin "34") (pinfunction "GND_34") (pintype "power_in"))
      (node (ref "IC2") (pin "14") (pinfunction "GND_14") (pintype "power_in"))
      (node (ref "IC2B") (pin "12") (pinfunction "GND_12") (pintype "power_in"))
      (node (ref "IC3") (pin "29") (pinfunction "GND_29") (pintype "power_in"))
      (node (ref "IC4") (pin "14") (pinfunction "GND_14") (pintype "power_in"))
      (node (ref "IC4A") (pin "9") (pinfunction "GND_9") (pintype "power_in"))
      (node (ref "IC4B") (pin "9") (pinfunction "GND_9") (pintype "power_in"))
      (node (ref "JP1") (pin "1") (pinfunction "P$1_1") (pintype "bidirectional"))
      (node (ref "JP2") (pin "1") (pinfunction "P$1_1") (pintype "bidirectional"))
      (node (ref "K1") (pin "B4") (pinfunction "4B_B4") (pintype "bidirectional"))
      (node (ref "K1") (pin "B5") (pinfunction "5B_B5") (pintype "bidirectional"))
      (node (ref "K2") (pin "2") (pinfunction "P$2_2") (pintype "bidirectional"))
      (node (ref "K3") (pin "2") (pinfunction "P$2_2") (pintype "bidirectional"))
      (node (ref "K4") (pin "2") (pinfunction "P$2_2") (pintype "bidirectional"))
      (node (ref "K5") (pin "7") (pinfunction "7_7") (pintype "bidirectional"))
      (node (ref "K5") (pin "8") (pinfunction "8_8") (pintype "bidirectional"))
      (node (ref "R27") (pin "1") (pinfunction "1_1") (pintype "passive"))
      (node (ref "R3") (pin "1") (pinfunction "1_1") (pintype "passive"))
      (node (ref "R30") (pin "2") (pinfunction "2_2") (pintype "passive"))
      (node (ref "R31") (pin "1") (pinfunction "1_1") (pintype "passive"))
      (node (ref "R34") (pin "1") (pinfunction "1_1") (pintype "passive"))
      (node (ref "R4") (pin "1") (pinfunction "1_1") (pintype "passive"))
      (node (ref "REG1") (pin "GND") (pinfunction "GND_GND") (pintype "input"))
      (node (ref "T2") (pin "E") (pinfunction "E_E") (pintype "passive"))
      (node (ref "X1") (pin "1") (pinfunction "1_1") (pintype "passive"))
    )
    (net (code "73") (name "Net-(C6-Pad2)") (class "Default")
      (node (ref "C6") (pin "2") (pinfunction "2_2") (pintype "passive"))
      (node (ref "X1") (pin "2") (pinfunction "2_2") (pintype "passive"))
    )
    (net (code "74") (name "Net-(C7-Pad2)") (class "Default")
      (node (ref "C7") (pin "2") (pinfunction "2_2") (pintype "passive"))
      (node (ref "R3") (pin "2") (pinfunction "2_2") (pintype "passive"))
      (node (ref "R6") (pin "2") (pinfunction "2_2") (pintype "passive"))
      (node (ref "T2") (pin "B") (pinfunction "B_B") (pintype "passive"))
    )
    (net (code "75") (name "Net-(C10-Pad2)") (class "Default")
      (node (ref "C10") (pin "2") (pinfunction "2_2") (pintype "passive"))
      (node (ref "R33") (pin "1") (pinfunction "1_1") (pintype "passive"))
    )
    (net (code "76") (name "Net-(C12-Pad2)") (class "Default")
      (node (ref "C12") (pin "2") (pinfunction "2_2") (pintype "passive"))
      (node (ref "R29") (pin "1") (pinfunction "1_1") (pintype "passive"))
    )
    (net (code "77") (name "Net-(D9-PadC)") (class "Default")
      (node (ref "D9") (pin "C") (pinfunction "C_C") (pintype "passive"))
      (node (ref "R32") (pin "2") (pinfunction "2_2") (pintype "passive"))
    )
    (net (code "78") (name "Net-(IC1-KBD0)") (class "Default")
      (node (ref "IC1") (pin "33") (pinfunction "KBD0_33") (pintype "output"))
      (node (ref "KB1") (pin "P$1") (pinfunction "1_P$1") (pintype "bidirectional"))
      (node (ref "RP3") (pin "2") (pinfunction "2_2") (pintype "passive"))
    )
    (net (code "79") (name "Net-(IC1-KBD1)") (class "Default")
      (node (ref "IC1") (pin "31") (pinfunction "KBD1_31") (pintype "input"))
      (node (ref "KB1") (pin "P$2") (pinfunction "2_P$2") (pintype "bidirectional"))
      (node (ref "RP3") (pin "3") (pinfunction "3_3") (pintype "passive"))
    )
    (net (code "80") (name "Net-(IC1-KBD2)") (class "Default")
      (node (ref "IC1") (pin "29") (pinfunction "KBD2_29") (pintype "input"))
      (node (ref "KB1") (pin "P$3") (pinfunction "3_P$3") (pintype "bidirectional"))
      (node (ref "RP3") (pin "4") (pinfunction "4_4") (pintype "passive"))
    )
    (net (code "81") (name "Net-(IC1-KBD3)") (class "Default")
      (node (ref "IC1") (pin "27") (pinfunction "KBD3_27") (pintype "input"))
      (node (ref "KB1") (pin "P$4") (pinfunction "4_P$4") (pintype "bidirectional"))
      (node (ref "RP3") (pin "5") (pinfunction "5_5") (pintype "passive"))
    )
    (net (code "82") (name "Net-(IC1-KBD4)") (class "Default")
      (node (ref "IC1") (pin "25") (pinfunction "KBD4_25") (pintype "input"))
      (node (ref "KB1") (pin "P$5") (pinfunction "5_P$5") (pintype "bidirectional"))
      (node (ref "RP3") (pin "6") (pinfunction "6_6") (pintype "passive"))
    )
    (net (code "83") (name "Net-(IC1-OSC)") (class "Default")
      (node (ref "C6") (pin "1") (pinfunction "1_1") (pintype "passive"))
      (node (ref "IC1") (pin "35") (pinfunction "OSC_35") (pintype "output"))
      (node (ref "JP3") (pin "1") (pinfunction "P$1_1") (pintype "bidirectional"))
      (node (ref "R4") (pin "2") (pinfunction "2_2") (pintype "passive"))
    )
    (net (code "84") (name "Net-(IC1-RAMCS)") (class "Default")
      (node (ref "IC1") (pin "12") (pinfunction "RAMCS_12") (pintype "output"))
      (node (ref "R2") (pin "1") (pinfunction "1_1") (pintype "passive"))
    )
    (net (code "85") (name "Net-(IC1-ROMCS)") (class "Default")
      (node (ref "IC1") (pin "13") (pinfunction "ROMCS_13") (pintype "output"))
      (node (ref "R28") (pin "1") (pinfunction "1_1") (pintype "passive"))
    )
    (net (code "86") (name "Net-(IC1-TAPE_IN)") (class "Default")
      (node (ref "IC1") (pin "20") (pinfunction "TAPE_IN_20") (pintype "output"))
      (node (ref "R33") (pin "2") (pinfunction "2_2") (pintype "passive"))
    )
    (net (code "87") (name "Net-(IC2-A14)") (class "Default")
      (node (ref "IC2") (pin "27") (pinfunction "A14_27") (pintype "input"))
      (node (ref "JP1") (pin "2") (pinfunction "P$2_2") (pintype "bidirectional"))
      (node (ref "R80") (pin "1") (pinfunction "1_1") (pintype "passive"))
    )
    (net (code "88") (name "Net-(IC2-A15)") (class "Default")
      (node (ref "IC2") (pin "1") (pinfunction "A15_1") (pintype "input"))
      (node (ref "JP2") (pin "2") (pinfunction "P$2_2") (pintype "bidirectional"))
      (node (ref "R81") (pin "1") (pinfunction "1_1") (pintype "passive"))
    )
    (net (code "89") (name "Net-(JP4-P$1)") (class "Default")
      (node (ref "C1") (pin "2") (pinfunction "2_2") (pintype "passive"))
      (node (ref "JP4") (pin "1") (pinfunction "P$1_1") (pintype "bidirectional"))
      (node (ref "R1") (pin "2") (pinfunction "2_2") (pintype "passive"))
      (node (ref "T1") (pin "B") (pinfunction "B_B") (pintype "passive"))
    )
    (net (code "90") (name "Net-(JP4-P$2)") (class "Default")
      (node (ref "JP4") (pin "2") (pinfunction "P$2_2") (pintype "bidirectional"))
      (node (ref "T3") (pin "C") (pinfunction "C_C") (pintype "passive"))
    )
    (net (code "91") (name "Net-(K2-P$1')") (class "Default")
      (node (ref "C11") (pin "1") (pinfunction "1_1") (pintype "passive"))
      (node (ref "C12") (pin "1") (pinfunction "1_1") (pintype "passive"))
      (node (ref "K2") (pin "1") (pinfunction "P$1_1") (pintype "bidirectional"))
      (node (ref "K2") (pin "1'") (pinfunction "P$1'_1'") (pintype "bidirectional"))
      (node (ref "R27") (pin "2") (pinfunction "2_2") (pintype "passive"))
    )
    (net (code "92") (name "Net-(KB2-1)") (class "Default")
      (node (ref "D1") (pin "A") (pinfunction "A_A") (pintype "passive"))
      (node (ref "KB2") (pin "P$1") (pinfunction "1_P$1") (pintype "bidirectional"))
    )
    (net (code "93") (name "Net-(KB2-2)") (class "Default")
      (node (ref "D2") (pin "A") (pinfunction "A_A") (pintype "passive"))
      (node (ref "KB2") (pin "P$2") (pinfunction "2_P$2") (pintype "bidirectional"))
    )
    (net (code "94") (name "Net-(KB2-3)") (class "Default")
      (node (ref "D3") (pin "A") (pinfunction "A_A") (pintype "passive"))
      (node (ref "KB2") (pin "P$3") (pinfunction "3_P$3") (pintype "bidirectional"))
    )
    (net (code "95") (name "Net-(KB2-4)") (class "Default")
      (node (ref "D4") (pin "A") (pinfunction "A_A") (pintype "passive"))
      (node (ref "KB2") (pin "P$4") (pinfunction "4_P$4") (pintype "bidirectional"))
    )
    (net (code "96") (name "Net-(KB2-5)") (class "Default")
      (node (ref "D5") (pin "A") (pinfunction "A_A") (pintype "passive"))
      (node (ref "KB2") (pin "P$5") (pinfunction "5_P$5") (pintype "bidirectional"))
    )
    (net (code "97") (name "Net-(KB2-6)") (class "Default")
      (node (ref "D6") (pin "A") (pinfunction "A_A") (pintype "passive"))
      (node (ref "KB2") (pin "P$6") (pinfunction "6_P$6") (pintype "bidirectional"))
    )
    (net (code "98") (name "Net-(KB2-7)") (class "Default")
      (node (ref "D7") (pin "A") (pinfunction "A_A") (pintype "passive"))
      (node (ref "KB2") (pin "P$7") (pinfunction "7_P$7") (pintype "bidirectional"))
    )
    (net (code "99") (name "Net-(KB2-8)") (class "Default")
      (node (ref "D8") (pin "A") (pinfunction "A_A") (pintype "passive"))
      (node (ref "KB2") (pin "P$8") (pinfunction "8_P$8") (pintype "bidirectional"))
    )
    (net (code "100") (name "Net-(R31-Pad2)") (class "Default")
      (node (ref "R31") (pin "2") (pinfunction "2_2") (pintype "passive"))
      (node (ref "R32") (pin "1") (pinfunction "1_1") (pintype "passive"))
    )
    (net (code "101") (name "Net-(R35-Pad1)") (class "Default")
      (node (ref "R35") (pin "1") (pinfunction "1_1") (pintype "passive"))
      (node (ref "T3") (pin "E") (pinfunction "E_E") (pintype "passive"))
    )
  )
)
